# tpic-words.net
KiCad netlist of a schematic drawn in EAGLE
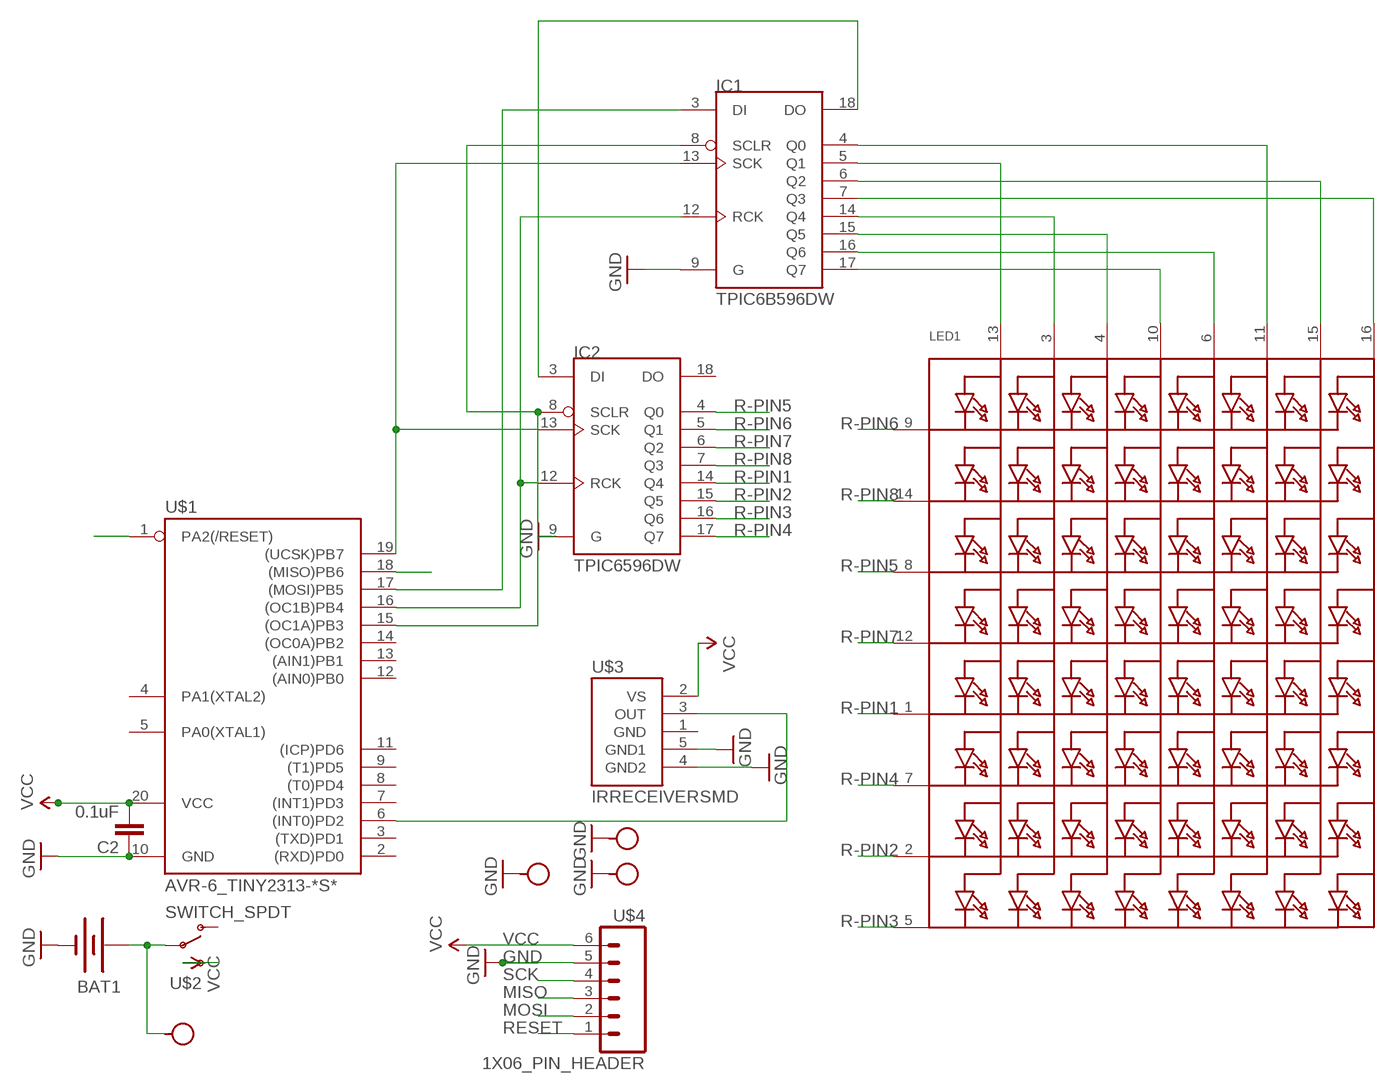
[diagram p0: schematic, sheet 1]

(export (version "E")
  (design (tool "Eeschema 10.0.6"))
  (components
    (comp (ref "BAT1")
      (value "NSL_SPARKFUN_BATTERY")
      (footprint "eagle-import:NSL_BATTICON_20MM_CLIPPED")
      (libsource (lib "eagle-import") (part "NSL_SPARKFUN_BATTERY"))
    )
    (comp (ref "C2")
      (value "0.1uF")
      (footprint "eagle-import:0402-CAP")
      (libsource (lib "eagle-import") (part ".1UF-CER"))
    )
    (comp (ref "H1")
      (value "SEW_HOLE-SMALL")
      (footprint "eagle-import:SIMPLE_HOLE_SM")
      (libsource (lib "eagle-import") (part "SEW_HOLE-SMALL"))
    )
    (comp (ref "H2")
      (value "SEW_HOLE-SMALL")
      (footprint "eagle-import:SIMPLE_HOLE_SM")
      (libsource (lib "eagle-import") (part "SEW_HOLE-SMALL"))
    )
    (comp (ref "H3")
      (value "SEW_HOLE-SMALL")
      (footprint "eagle-import:SIMPLE_HOLE_SM")
      (libsource (lib "eagle-import") (part "SEW_HOLE-SMALL"))
    )
    (comp (ref "H4")
      (value "SEW_HOLE-SMALL")
      (footprint "eagle-import:SIMPLE_HOLE_SM")
      (libsource (lib "eagle-import") (part "SEW_HOLE-SMALL"))
    )
    (comp (ref "IC1")
      (value "TPIC6B596DW")
      (footprint "eagle-import:SO20W")
      (libsource (lib "eagle-import") (part "TPIC6B596DW"))
    )
    (comp (ref "IC2")
      (value "TPIC6596DW")
      (footprint "eagle-import:SO20W")
      (libsource (lib "eagle-import") (part "TPIC6596DW"))
    )
    (comp (ref "LED1")
      (value "SEGMENT_8X8_ROWCATHODESEG-HEADERS")
      (footprint "eagle-import:SEGMENT-HEADERS")
      (libsource (lib "eagle-import") (part "SEGMENT_8X8_ROWCATHODESEG-HEADERS"))
    )
    (comp (ref "U$1")
      (value "AVR-6_TINY2313-*S*")
      (footprint "eagle-import:AVR-6_SO20L$")
      (libsource (lib "eagle-import") (part "AVR-6_TINY2313-S"))
    )
    (comp (ref "U$2")
      (value "SWITCH_SPDT")
      (footprint "eagle-import:KPS-1290")
      (libsource (lib "eagle-import") (part "SWITCH_SPDT"))
    )
    (comp (ref "U$3")
      (value "IRRECEIVERSMD")
      (footprint "eagle-import:TSOP8523")
      (libsource (lib "eagle-import") (part "IRRECEIVERSMD"))
    )
    (comp (ref "U$4")
      (value "1X06_PIN_HEADER")
      (footprint "eagle-import:1X06_EDGE")
      (libsource (lib "eagle-import") (part "1X06_PIN_HEADER"))
    )
  )
  (nets
    (net (code "1") (name "/MISO") (class "Default")
      (node (ref "U$1") (pin "18") (pinfunction "(MISO)PB6_18") (pintype "bidirectional"))
      (node (ref "U$4") (pin "3") (pinfunction "3_3") (pintype "passive"))
    )
    (net (code "2") (name "/MOSI") (class "Default")
      (node (ref "IC1") (pin "3") (pinfunction "DI_3") (pintype "input"))
      (node (ref "U$1") (pin "17") (pinfunction "(MOSI)PB5_17") (pintype "bidirectional"))
      (node (ref "U$4") (pin "2") (pinfunction "2_2") (pintype "passive"))
    )
    (net (code "3") (name "/R-PIN1") (class "Default")
      (node (ref "IC2") (pin "14") (pinfunction "Q4_14") (pintype "open_collector"))
      (node (ref "LED1") (pin "1") (pinfunction "K5_1") (pintype "bidirectional"))
    )
    (net (code "4") (name "/R-PIN2") (class "Default")
      (node (ref "IC2") (pin "15") (pinfunction "Q5_15") (pintype "open_collector"))
      (node (ref "LED1") (pin "2") (pinfunction "K7_2") (pintype "bidirectional"))
    )
    (net (code "5") (name "/R-PIN3") (class "Default")
      (node (ref "IC2") (pin "16") (pinfunction "Q6_16") (pintype "open_collector"))
      (node (ref "LED1") (pin "5") (pinfunction "K8_5") (pintype "bidirectional"))
    )
    (net (code "6") (name "/R-PIN4") (class "Default")
      (node (ref "IC2") (pin "17") (pinfunction "Q7_17") (pintype "open_collector"))
      (node (ref "LED1") (pin "7") (pinfunction "K6_7") (pintype "bidirectional"))
    )
    (net (code "7") (name "/R-PIN5") (class "Default")
      (node (ref "IC2") (pin "4") (pinfunction "Q0_4") (pintype "open_collector"))
      (node (ref "LED1") (pin "8") (pinfunction "K3_8") (pintype "bidirectional"))
    )
    (net (code "8") (name "/R-PIN6") (class "Default")
      (node (ref "IC2") (pin "5") (pinfunction "Q1_5") (pintype "open_collector"))
      (node (ref "LED1") (pin "9") (pinfunction "K1_9") (pintype "bidirectional"))
    )
    (net (code "9") (name "/R-PIN7") (class "Default")
      (node (ref "IC2") (pin "6") (pinfunction "Q2_6") (pintype "open_collector"))
      (node (ref "LED1") (pin "12") (pinfunction "K4_12") (pintype "bidirectional"))
    )
    (net (code "10") (name "/R-PIN8") (class "Default")
      (node (ref "IC2") (pin "7") (pinfunction "Q3_7") (pintype "open_collector"))
      (node (ref "LED1") (pin "14") (pinfunction "K2_14") (pintype "bidirectional"))
    )
    (net (code "11") (name "/RESET") (class "Default")
      (node (ref "U$1") (pin "1") (pinfunction "PA2(/RESET)_1") (pintype "input"))
      (node (ref "U$4") (pin "1") (pinfunction "1_1") (pintype "passive"))
    )
    (net (code "12") (name "/SCK") (class "Default")
      (node (ref "IC1") (pin "13") (pinfunction "SCK_13") (pintype "input"))
      (node (ref "IC2") (pin "13") (pinfunction "SCK_13") (pintype "input"))
      (node (ref "U$1") (pin "19") (pinfunction "(UCSK)PB7_19") (pintype "bidirectional"))
      (node (ref "U$4") (pin "4") (pinfunction "4_4") (pintype "passive"))
    )
    (net (code "13") (name "GND") (class "Default")
      (node (ref "BAT1") (pin "2") (pinfunction "-_2") (pintype "power_in"))
      (node (ref "C2") (pin "1") (pinfunction "1_1") (pintype "passive"))
      (node (ref "H1") (pin "P$1") (pinfunction "P$1_P$1") (pintype "bidirectional"))
      (node (ref "H3") (pin "P$1") (pinfunction "P$1_P$1") (pintype "bidirectional"))
      (node (ref "H4") (pin "P$1") (pinfunction "P$1_P$1") (pintype "bidirectional"))
      (node (ref "IC1") (pin "9") (pinfunction "G_9") (pintype "input"))
      (node (ref "IC2") (pin "9") (pinfunction "G_9") (pintype "input"))
      (node (ref "U$1") (pin "10") (pinfunction "GND_10") (pintype "power_in"))
      (node (ref "U$3") (pin "4") (pinfunction "GND2_4") (pintype "bidirectional"))
      (node (ref "U$3") (pin "5") (pinfunction "GND1_5") (pintype "bidirectional"))
      (node (ref "U$4") (pin "5") (pinfunction "5_5") (pintype "passive"))
    )
    (net (code "14") (name "Net-(BAT1-+)") (class "Default")
      (node (ref "BAT1") (pin "1") (pinfunction "+_1") (pintype "power_in"))
      (node (ref "H2") (pin "P$1") (pinfunction "P$1_P$1") (pintype "bidirectional"))
      (node (ref "U$2") (pin "P") (pinfunction "P_P") (pintype "passive"))
    )
    (net (code "15") (name "Net-(IC1A-DO)") (class "Default")
      (node (ref "IC1") (pin "18") (pinfunction "DO_18") (pintype "output"))
      (node (ref "IC2") (pin "3") (pinfunction "DI_3") (pintype "input"))
    )
    (net (code "16") (name "Net-(IC1A-Q0)") (class "Default")
      (node (ref "IC1") (pin "4") (pinfunction "Q0_4") (pintype "open_collector"))
      (node (ref "LED1") (pin "11") (pinfunction "A6_11") (pintype "bidirectional"))
    )
    (net (code "17") (name "Net-(IC1A-Q1)") (class "Default")
      (node (ref "IC1") (pin "5") (pinfunction "Q1_5") (pintype "open_collector"))
      (node (ref "LED1") (pin "13") (pinfunction "A1_13") (pintype "bidirectional"))
    )
    (net (code "18") (name "Net-(IC1A-Q2)") (class "Default")
      (node (ref "IC1") (pin "6") (pinfunction "Q2_6") (pintype "open_collector"))
      (node (ref "LED1") (pin "15") (pinfunction "A7_15") (pintype "bidirectional"))
    )
    (net (code "19") (name "Net-(IC1A-Q3)") (class "Default")
      (node (ref "IC1") (pin "7") (pinfunction "Q3_7") (pintype "open_collector"))
      (node (ref "LED1") (pin "16") (pinfunction "A8_16") (pintype "bidirectional"))
    )
    (net (code "20") (name "Net-(IC1A-Q4)") (class "Default")
      (node (ref "IC1") (pin "14") (pinfunction "Q4_14") (pintype "open_collector"))
      (node (ref "LED1") (pin "3") (pinfunction "A2_3") (pintype "bidirectional"))
    )
    (net (code "21") (name "Net-(IC1A-Q5)") (class "Default")
      (node (ref "IC1") (pin "15") (pinfunction "Q5_15") (pintype "open_collector"))
      (node (ref "LED1") (pin "4") (pinfunction "A3_4") (pintype "bidirectional"))
    )
    (net (code "22") (name "Net-(IC1A-Q6)") (class "Default")
      (node (ref "IC1") (pin "16") (pinfunction "Q6_16") (pintype "open_collector"))
      (node (ref "LED1") (pin "6") (pinfunction "A5_6") (pintype "bidirectional"))
    )
    (net (code "23") (name "Net-(IC1A-Q7)") (class "Default")
      (node (ref "IC1") (pin "17") (pinfunction "Q7_17") (pintype "open_collector"))
      (node (ref "LED1") (pin "10") (pinfunction "A4_10") (pintype "bidirectional"))
    )
    (net (code "24") (name "Net-(IC1A-RCK)") (class "Default")
      (node (ref "IC1") (pin "12") (pinfunction "RCK_12") (pintype "input"))
      (node (ref "IC2") (pin "12") (pinfunction "RCK_12") (pintype "input"))
      (node (ref "U$1") (pin "16") (pinfunction "(OC1B)PB4_16") (pintype "bidirectional"))
    )
    (net (code "25") (name "Net-(IC1A-SCLR)") (class "Default")
      (node (ref "IC1") (pin "8") (pinfunction "SCLR_8") (pintype "input"))
      (node (ref "IC2") (pin "8") (pinfunction "SCLR_8") (pintype "input"))
      (node (ref "U$1") (pin "15") (pinfunction "(OC1A)PB3_15") (pintype "bidirectional"))
    )
    (net (code "26") (name "Net-(U$1-(INT0)PD2)") (class "Default")
      (node (ref "U$1") (pin "6") (pinfunction "(INT0)PD2_6") (pintype "bidirectional"))
      (node (ref "U$3") (pin "3") (pinfunction "OUT_3") (pintype "bidirectional"))
    )
    (net (code "27") (name "VCC") (class "Default")
      (node (ref "C2") (pin "2") (pinfunction "2_2") (pintype "passive"))
      (node (ref "U$1") (pin "20") (pinfunction "VCC_20") (pintype "power_in"))
      (node (ref "U$2") (pin "S") (pinfunction "S_S") (pintype "passive"))
      (node (ref "U$3") (pin "2") (pinfunction "VS_2") (pintype "bidirectional"))
      (node (ref "U$4") (pin "6") (pinfunction "6_6") (pintype "passive"))
    )
    (net (code "28") (name "unconnected-(IC2A-DO-Pad18)") (class "Default")
      (node (ref "IC2") (pin "18") (pinfunction "DO_18") (pintype "output"))
    )
    (net (code "29") (name "unconnected-(U$1-(AIN0)PB0-Pad12)") (class "Default")
      (node (ref "U$1") (pin "12") (pinfunction "(AIN0)PB0_12") (pintype "bidirectional"))
    )
    (net (code "30") (name "unconnected-(U$1-(AIN1)PB1-Pad13)") (class "Default")
      (node (ref "U$1") (pin "13") (pinfunction "(AIN1)PB1_13") (pintype "bidirectional"))
    )
    (net (code "31") (name "unconnected-(U$1-(ICP)PD6-Pad11)") (class "Default")
      (node (ref "U$1") (pin "11") (pinfunction "(ICP)PD6_11") (pintype "bidirectional"))
    )
    (net (code "32") (name "unconnected-(U$1-(INT1)PD3-Pad7)") (class "Default")
      (node (ref "U$1") (pin "7") (pinfunction "(INT1)PD3_7") (pintype "bidirectional"))
    )
    (net (code "33") (name "unconnected-(U$1-(OC0A)PB2-Pad14)") (class "Default")
      (node (ref "U$1") (pin "14") (pinfunction "(OC0A)PB2_14") (pintype "bidirectional"))
    )
    (net (code "34") (name "unconnected-(U$1-(RXD)PD0-Pad2)") (class "Default")
      (node (ref "U$1") (pin "2") (pinfunction "(RXD)PD0_2") (pintype "bidirectional"))
    )
    (net (code "35") (name "unconnected-(U$1-(T0)PD4-Pad8)") (class "Default")
      (node (ref "U$1") (pin "8") (pinfunction "(T0)PD4_8") (pintype "bidirectional"))
    )
    (net (code "36") (name "unconnected-(U$1-(T1)PD5-Pad9)") (class "Default")
      (node (ref "U$1") (pin "9") (pinfunction "(T1)PD5_9") (pintype "bidirectional"))
    )
    (net (code "37") (name "unconnected-(U$1-(TXD)PD1-Pad3)") (class "Default")
      (node (ref "U$1") (pin "3") (pinfunction "(TXD)PD1_3") (pintype "bidirectional"))
    )
    (net (code "38") (name "unconnected-(U$1-PA0(XTAL1)-Pad5)") (class "Default")
      (node (ref "U$1") (pin "5") (pinfunction "PA0(XTAL1)_5") (pintype "bidirectional"))
    )
    (net (code "39") (name "unconnected-(U$1-PA1(XTAL2)-Pad4)") (class "Default")
      (node (ref "U$1") (pin "4") (pinfunction "PA1(XTAL2)_4") (pintype "bidirectional"))
    )
    (net (code "40") (name "unconnected-(U$2-PadO)") (class "Default")
      (node (ref "U$2") (pin "O") (pinfunction "O_O") (pintype "passive"))
    )
    (net (code "41") (name "unconnected-(U$3-GND-Pad1)") (class "Default")
      (node (ref "U$3") (pin "1") (pinfunction "GND_1") (pintype "bidirectional"))
    )
  )
)
